# 02_memory.net
KiCad netlist of a schematic drawn in Altium Designer
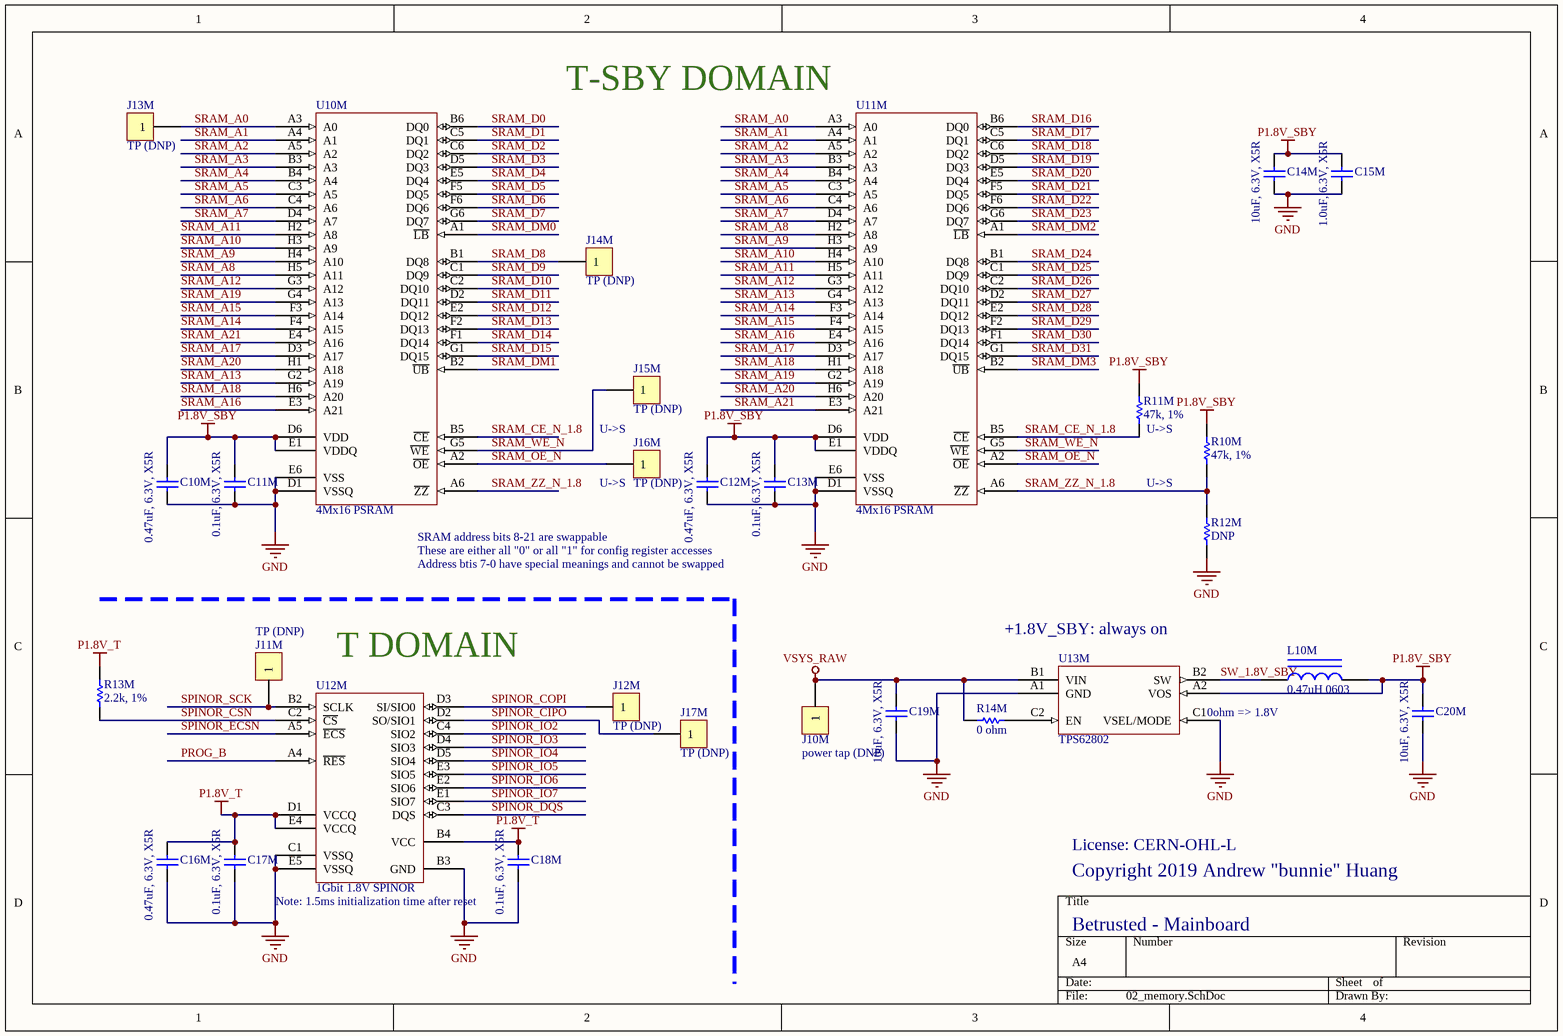
[diagram p0: 02_memory.SchDoc]

(export (version "E")
  (design (tool "Eeschema 10.0.6"))
  (components
    (comp (ref "C10M")
      (value "0.47uF, 6.3V, X5R")
      (footprint "B_CAP0201")
      (description "Capacitor (Semiconductor SIM Model)")
      (fields (field (name "MPN") "CL03A474KQ3NNNH"))
      (libsource (lib "Miscellaneous Devices") (part "Cap Semi"))
    )
    (comp (ref "C11M")
      (value "0.1uF, 6.3V, X5R")
      (footprint "B_CAP0201")
      (description "Capacitor (Semiconductor SIM Model)")
      (fields (field (name "MPN") "CL03A104KQ3NNNC"))
      (libsource (lib "Miscellaneous Devices") (part "Cap Semi"))
    )
    (comp (ref "C12M")
      (value "0.47uF, 6.3V, X5R")
      (footprint "B_CAP0201")
      (description "Capacitor (Semiconductor SIM Model)")
      (fields (field (name "MPN") "CL03A474KQ3NNNH"))
      (libsource (lib "Miscellaneous Devices") (part "Cap Semi"))
    )
    (comp (ref "C13M")
      (value "0.1uF, 6.3V, X5R")
      (footprint "B_CAP0201")
      (description "Capacitor (Semiconductor SIM Model)")
      (fields (field (name "MPN") "CL03A104KQ3NNNC"))
      (libsource (lib "Miscellaneous Devices") (part "Cap Semi"))
    )
    (comp (ref "C14M")
      (value "10uF, 6.3V, X5R")
      (footprint "B_CAP0603")
      (description "Capacitor (Semiconductor SIM Model)")
      (fields (field (name "MPN") "CL10A106MQ8NNNC"))
      (libsource (lib "Miscellaneous Devices") (part "Cap Semi"))
    )
    (comp (ref "C15M")
      (value "1.0uF, 6.3V, X5R")
      (footprint "B_CAP0201")
      (description "Capacitor (Semiconductor SIM Model)")
      (fields (field (name "MPN") "GRM033R60J105MEA2D"))
      (libsource (lib "Miscellaneous Devices") (part "Cap Semi"))
    )
    (comp (ref "C16M")
      (value "0.47uF, 6.3V, X5R")
      (footprint "B_CAP0201")
      (description "Capacitor (Semiconductor SIM Model)")
      (fields (field (name "MPN") "CL03A474KQ3NNNH"))
      (libsource (lib "Miscellaneous Devices") (part "Cap Semi"))
    )
    (comp (ref "C17M")
      (value "0.1uF, 6.3V, X5R")
      (footprint "B_CAP0201")
      (description "Capacitor (Semiconductor SIM Model)")
      (fields (field (name "MPN") "CL03A104KQ3NNNC"))
      (libsource (lib "Miscellaneous Devices") (part "Cap Semi"))
    )
    (comp (ref "C18M")
      (value "0.1uF, 6.3V, X5R")
      (footprint "B_CAP0201")
      (description "Capacitor (Semiconductor SIM Model)")
      (fields (field (name "MPN") "CL03A104KQ3NNNC"))
      (libsource (lib "Miscellaneous Devices") (part "Cap Semi"))
    )
    (comp (ref "C19M")
      (value "10uF, 6.3V, X5R")
      (footprint "B_CAP0603")
      (description "Capacitor (Semiconductor SIM Model)")
      (fields (field (name "MPN") "CL10A106MQ8NNNC"))
      (libsource (lib "Miscellaneous Devices") (part "Cap Semi"))
    )
    (comp (ref "C20M")
      (value "10uF, 6.3V, X5R")
      (footprint "B_CAP0603")
      (description "Capacitor (Semiconductor SIM Model)")
      (fields (field (name "MPN") "CL10A106MQ8NNNC"))
      (libsource (lib "Miscellaneous Devices") (part "Cap Semi"))
    )
    (comp (ref "J10M")
      (value "power tap (DNP)")
      (footprint "RESTAP-0603")
      (description "Connector")
      (fields (field (name "MPN") "DNP"))
      (libsource (lib "") (part "CON1_2"))
    )
    (comp (ref "J11M")
      (value "TP (DNP)")
      (footprint "TP_0.4x0.4_SMT")
      (description "Connector")
      (fields (field (name "MPN") "DNP"))
      (libsource (lib "") (part "CON1_1"))
    )
    (comp (ref "J12M")
      (value "TP (DNP)")
      (footprint "TP_0.4x0.4_SMT")
      (description "Connector")
      (fields (field (name "MPN") "DNP"))
      (libsource (lib "*") (part "CON1"))
    )
    (comp (ref "J13M")
      (value "TP (DNP)")
      (footprint "TP_0.4x0.4_SMT")
      (description "Connector")
      (fields (field (name "MPN") "DNP"))
      (libsource (lib "") (part "CON1_3"))
    )
    (comp (ref "J14M")
      (value "TP (DNP)")
      (footprint "TP_0.4x0.4_SMT")
      (description "Connector")
      (fields (field (name "MPN") "DNP"))
      (libsource (lib "*") (part "CON1"))
    )
    (comp (ref "J15M")
      (value "TP (DNP)")
      (footprint "TP_0.4x0.4_SMT")
      (description "Connector")
      (fields (field (name "MPN") "DNP"))
      (libsource (lib "*") (part "CON1"))
    )
    (comp (ref "J16M")
      (value "TP (DNP)")
      (footprint "TP_0.4x0.4_SMT")
      (description "Connector")
      (fields (field (name "MPN") "DNP"))
      (libsource (lib "*") (part "CON1"))
    )
    (comp (ref "J17M")
      (value "TP (DNP)")
      (footprint "TP_0.4x0.4_SMT")
      (description "Connector")
      (fields (field (name "MPN") "DNP"))
      (libsource (lib "*") (part "CON1"))
    )
    (comp (ref "L10M")
      (value "0.47uH 0603")
      (footprint "B_IND0603")
      (description "Magnetic-Core Inductor")
      (fields (field (name "MPN") "TFM160808ALC-R47MTAA"))
      (libsource (lib "Miscellaneous Devices") (part "Inductor Iron"))
    )
    (comp (ref "R10M")
      (value "47k, 1%")
      (footprint "B_RES0201")
      (description "Resistor")
      (fields (field (name "MPN") "ANY"))
      (libsource (lib "Miscellaneous Devices") (part "Res1"))
    )
    (comp (ref "R11M")
      (value "47k, 1%")
      (footprint "B_RES0201")
      (description "Resistor")
      (fields (field (name "MPN") "ANY"))
      (libsource (lib "Miscellaneous Devices") (part "Res1"))
    )
    (comp (ref "R12M")
      (value "DNP")
      (footprint "B_RES0201")
      (description "Resistor")
      (fields (field (name "MPN") "ANY"))
      (libsource (lib "Miscellaneous Devices") (part "Res1"))
    )
    (comp (ref "R13M")
      (value "2.2k, 1%")
      (footprint "B_RES0201")
      (description "Resistor")
      (fields (field (name "MPN") "ANY"))
      (libsource (lib "Miscellaneous Devices") (part "Res1"))
    )
    (comp (ref "R14M")
      (value "0 ohm")
      (footprint "B_RES0201")
      (description "Resistor")
      (fields (field (name "MPN") "ANY"))
      (libsource (lib "Miscellaneous Devices") (part "Res1"))
    )
    (comp (ref "U10M")
      (value "4Mx16 PSRAM")
      (footprint "BGA48C75P6X8_600X800X120")
      (fields (field (name "MPN") "IS66WVE4M16EALL-70BLI"))
      (libsource (lib "altium-import") (part "root_0_IS66WVE4M16_"))
    )
    (comp (ref "U11M")
      (value "4Mx16 PSRAM")
      (footprint "BGA48C75P6X8_600X800X120")
      (fields (field (name "MPN") "IS66WVE4M16EALL-70BLI"))
      (libsource (lib "altium-import") (part "root_0_IS66WVE4M16_"))
    )
    (comp (ref "U12M")
      (value "1Gbit 1.8V SPINOR")
      (footprint "BGA24C100P5X5_600X800X120")
      (description "1.8V 1Gbit x1/x8 OctaFlash SPINOR")
      (fields (field (name "MPN") "MX66UM1G45GXDI00"))
      (libsource (lib "commonsch-new") (part "MX66UM1G45G"))
    )
    (comp (ref "U13M")
      (value "TPS62802")
      (footprint "BGA6C35P2X3_70X105X40_NSMD")
      (description "Buck regulator, 4MHz, 0.6A, 1.8V-3.3V, low Iq")
      (fields (field (name "MPN") "TPS62802YKAR"))
      (libsource (lib "altium-import") (part "root_0_TPS62802_"))
    )
  )
  (nets
    (net (code "1") (name "/PROG_B") (class "Default")
      (node (ref "U12M") (pin "A4") (pinfunction "~{RES}_A4") (pintype "input"))
    )
    (net (code "2") (name "/SPINOR_CIPO") (class "Default")
      (node (ref "J17M") (pin "1") (pinfunction "1_1") (pintype "passive"))
      (node (ref "U12M") (pin "D2") (pinfunction "SO/SIO1_D2") (pintype "bidirectional"))
    )
    (net (code "3") (name "/SPINOR_COPI") (class "Default")
      (node (ref "J12M") (pin "1") (pinfunction "1_1") (pintype "passive"))
      (node (ref "U12M") (pin "D3") (pinfunction "SI/SIO0_D3") (pintype "bidirectional"))
    )
    (net (code "4") (name "/SPINOR_CSN") (class "Default")
      (node (ref "R13M") (pin "1") (pinfunction "1_1") (pintype "passive"))
      (node (ref "U12M") (pin "C2") (pinfunction "~{CS}_C2") (pintype "input"))
    )
    (net (code "5") (name "/SPINOR_DQS") (class "Default")
      (node (ref "U12M") (pin "C3") (pinfunction "DQS_C3") (pintype "bidirectional"))
    )
    (net (code "6") (name "/SPINOR_ECSN") (class "Default")
      (node (ref "U12M") (pin "A5") (pinfunction "~{ECS}_A5") (pintype "input"))
    )
    (net (code "7") (name "/SPINOR_IO2") (class "Default")
      (node (ref "U12M") (pin "C4") (pinfunction "SIO2_C4") (pintype "bidirectional"))
    )
    (net (code "8") (name "/SPINOR_IO3") (class "Default")
      (node (ref "U12M") (pin "D4") (pinfunction "SIO3_D4") (pintype "bidirectional"))
    )
    (net (code "9") (name "/SPINOR_IO4") (class "Default")
      (node (ref "U12M") (pin "D5") (pinfunction "SIO4_D5") (pintype "bidirectional"))
    )
    (net (code "10") (name "/SPINOR_IO5") (class "Default")
      (node (ref "U12M") (pin "E3") (pinfunction "SIO5_E3") (pintype "bidirectional"))
    )
    (net (code "11") (name "/SPINOR_IO6") (class "Default")
      (node (ref "U12M") (pin "E2") (pinfunction "SIO6_E2") (pintype "bidirectional"))
    )
    (net (code "12") (name "/SPINOR_IO7") (class "Default")
      (node (ref "U12M") (pin "E1") (pinfunction "SIO7_E1") (pintype "bidirectional"))
    )
    (net (code "13") (name "/SPINOR_SCK") (class "Default")
      (node (ref "J11M") (pin "1") (pinfunction "1_1") (pintype "passive"))
      (node (ref "U12M") (pin "B2") (pinfunction "SCLK_B2") (pintype "input"))
    )
    (net (code "14") (name "/SRAM_A0") (class "Default")
      (node (ref "J13M") (pin "1") (pinfunction "1_1") (pintype "passive"))
      (node (ref "U10M") (pin "A3") (pinfunction "A0_A3") (pintype "input"))
      (node (ref "U11M") (pin "A3") (pinfunction "A0_A3") (pintype "input"))
    )
    (net (code "15") (name "/SRAM_A1") (class "Default")
      (node (ref "U10M") (pin "A4") (pinfunction "A1_A4") (pintype "input"))
      (node (ref "U11M") (pin "A4") (pinfunction "A1_A4") (pintype "input"))
    )
    (net (code "16") (name "/SRAM_A2") (class "Default")
      (node (ref "U10M") (pin "A5") (pinfunction "A2_A5") (pintype "input"))
      (node (ref "U11M") (pin "A5") (pinfunction "A2_A5") (pintype "input"))
    )
    (net (code "17") (name "/SRAM_A3") (class "Default")
      (node (ref "U10M") (pin "B3") (pinfunction "A3_B3") (pintype "input"))
      (node (ref "U11M") (pin "B3") (pinfunction "A3_B3") (pintype "input"))
    )
    (net (code "18") (name "/SRAM_A4") (class "Default")
      (node (ref "U10M") (pin "B4") (pinfunction "A4_B4") (pintype "input"))
      (node (ref "U11M") (pin "B4") (pinfunction "A4_B4") (pintype "input"))
    )
    (net (code "19") (name "/SRAM_A5") (class "Default")
      (node (ref "U10M") (pin "C3") (pinfunction "A5_C3") (pintype "input"))
      (node (ref "U11M") (pin "C3") (pinfunction "A5_C3") (pintype "input"))
    )
    (net (code "20") (name "/SRAM_A6") (class "Default")
      (node (ref "U10M") (pin "C4") (pinfunction "A6_C4") (pintype "input"))
      (node (ref "U11M") (pin "C4") (pinfunction "A6_C4") (pintype "input"))
    )
    (net (code "21") (name "/SRAM_A7") (class "Default")
      (node (ref "U10M") (pin "D4") (pinfunction "A7_D4") (pintype "input"))
      (node (ref "U11M") (pin "D4") (pinfunction "A7_D4") (pintype "input"))
    )
    (net (code "22") (name "/SRAM_A8") (class "Default")
      (node (ref "U10M") (pin "H5") (pinfunction "A11_H5") (pintype "input"))
      (node (ref "U11M") (pin "H2") (pinfunction "A8_H2") (pintype "input"))
    )
    (net (code "23") (name "/SRAM_A9") (class "Default")
      (node (ref "U10M") (pin "H4") (pinfunction "A10_H4") (pintype "input"))
      (node (ref "U11M") (pin "H3") (pinfunction "A9_H3") (pintype "input"))
    )
    (net (code "24") (name "/SRAM_A10") (class "Default")
      (node (ref "U10M") (pin "H3") (pinfunction "A9_H3") (pintype "input"))
      (node (ref "U11M") (pin "H4") (pinfunction "A10_H4") (pintype "input"))
    )
    (net (code "25") (name "/SRAM_A11") (class "Default")
      (node (ref "U10M") (pin "H2") (pinfunction "A8_H2") (pintype "input"))
      (node (ref "U11M") (pin "H5") (pinfunction "A11_H5") (pintype "input"))
    )
    (net (code "26") (name "/SRAM_A12") (class "Default")
      (node (ref "U10M") (pin "G3") (pinfunction "A12_G3") (pintype "input"))
      (node (ref "U11M") (pin "G3") (pinfunction "A12_G3") (pintype "input"))
    )
    (net (code "27") (name "/SRAM_A13") (class "Default")
      (node (ref "U10M") (pin "G2") (pinfunction "A19_G2") (pintype "input"))
      (node (ref "U11M") (pin "G4") (pinfunction "A13_G4") (pintype "input"))
    )
    (net (code "28") (name "/SRAM_A14") (class "Default")
      (node (ref "U10M") (pin "F4") (pinfunction "A15_F4") (pintype "input"))
      (node (ref "U11M") (pin "F3") (pinfunction "A14_F3") (pintype "input"))
    )
    (net (code "29") (name "/SRAM_A15") (class "Default")
      (node (ref "U10M") (pin "F3") (pinfunction "A14_F3") (pintype "input"))
      (node (ref "U11M") (pin "F4") (pinfunction "A15_F4") (pintype "input"))
    )
    (net (code "30") (name "/SRAM_A16") (class "Default")
      (node (ref "U10M") (pin "E3") (pinfunction "A21_E3") (pintype "input"))
      (node (ref "U11M") (pin "E4") (pinfunction "A16_E4") (pintype "input"))
    )
    (net (code "31") (name "/SRAM_A17") (class "Default")
      (node (ref "U10M") (pin "D3") (pinfunction "A17_D3") (pintype "input"))
      (node (ref "U11M") (pin "D3") (pinfunction "A17_D3") (pintype "input"))
    )
    (net (code "32") (name "/SRAM_A18") (class "Default")
      (node (ref "U10M") (pin "H6") (pinfunction "A20_H6") (pintype "input"))
      (node (ref "U11M") (pin "H1") (pinfunction "A18_H1") (pintype "input"))
    )
    (net (code "33") (name "/SRAM_A19") (class "Default")
      (node (ref "U10M") (pin "G4") (pinfunction "A13_G4") (pintype "input"))
      (node (ref "U11M") (pin "G2") (pinfunction "A19_G2") (pintype "input"))
    )
    (net (code "34") (name "/SRAM_A20") (class "Default")
      (node (ref "U10M") (pin "H1") (pinfunction "A18_H1") (pintype "input"))
      (node (ref "U11M") (pin "H6") (pinfunction "A20_H6") (pintype "input"))
    )
    (net (code "35") (name "/SRAM_A21") (class "Default")
      (node (ref "U10M") (pin "E4") (pinfunction "A16_E4") (pintype "input"))
      (node (ref "U11M") (pin "E3") (pinfunction "A21_E3") (pintype "input"))
    )
    (net (code "36") (name "/SRAM_CE_N_1.8") (class "Default")
      (node (ref "R11M") (pin "2") (pinfunction "2_2") (pintype "passive"))
      (node (ref "U10M") (pin "B5") (pinfunction "~{CE}_B5") (pintype "input"))
      (node (ref "U11M") (pin "B5") (pinfunction "~{CE}_B5") (pintype "input"))
    )
    (net (code "37") (name "/SRAM_D0") (class "Default")
      (node (ref "U10M") (pin "B6") (pinfunction "DQ0_B6") (pintype "bidirectional"))
    )
    (net (code "38") (name "/SRAM_D1") (class "Default")
      (node (ref "U10M") (pin "C5") (pinfunction "DQ1_C5") (pintype "bidirectional"))
    )
    (net (code "39") (name "/SRAM_D2") (class "Default")
      (node (ref "U10M") (pin "C6") (pinfunction "DQ2_C6") (pintype "bidirectional"))
    )
    (net (code "40") (name "/SRAM_D3") (class "Default")
      (node (ref "U10M") (pin "D5") (pinfunction "DQ3_D5") (pintype "bidirectional"))
    )
    (net (code "41") (name "/SRAM_D4") (class "Default")
      (node (ref "U10M") (pin "E5") (pinfunction "DQ4_E5") (pintype "bidirectional"))
    )
    (net (code "42") (name "/SRAM_D5") (class "Default")
      (node (ref "U10M") (pin "F5") (pinfunction "DQ5_F5") (pintype "bidirectional"))
    )
    (net (code "43") (name "/SRAM_D6") (class "Default")
      (node (ref "U10M") (pin "F6") (pinfunction "DQ6_F6") (pintype "bidirectional"))
    )
    (net (code "44") (name "/SRAM_D7") (class "Default")
      (node (ref "U10M") (pin "G6") (pinfunction "DQ7_G6") (pintype "bidirectional"))
    )
    (net (code "45") (name "/SRAM_D8") (class "Default")
      (node (ref "J14M") (pin "1") (pinfunction "1_1") (pintype "passive"))
      (node (ref "U10M") (pin "B1") (pinfunction "DQ8_B1") (pintype "bidirectional"))
    )
    (net (code "46") (name "/SRAM_D9") (class "Default")
      (node (ref "U10M") (pin "C1") (pinfunction "DQ9_C1") (pintype "bidirectional"))
    )
    (net (code "47") (name "/SRAM_D10") (class "Default")
      (node (ref "U10M") (pin "C2") (pinfunction "DQ10_C2") (pintype "bidirectional"))
    )
    (net (code "48") (name "/SRAM_D11") (class "Default")
      (node (ref "U10M") (pin "D2") (pinfunction "DQ11_D2") (pintype "bidirectional"))
    )
    (net (code "49") (name "/SRAM_D12") (class "Default")
      (node (ref "U10M") (pin "E2") (pinfunction "DQ12_E2") (pintype "bidirectional"))
    )
    (net (code "50") (name "/SRAM_D13") (class "Default")
      (node (ref "U10M") (pin "F2") (pinfunction "DQ13_F2") (pintype "bidirectional"))
    )
    (net (code "51") (name "/SRAM_D14") (class "Default")
      (node (ref "U10M") (pin "F1") (pinfunction "DQ14_F1") (pintype "bidirectional"))
    )
    (net (code "52") (name "/SRAM_D15") (class "Default")
      (node (ref "U10M") (pin "G1") (pinfunction "DQ15_G1") (pintype "bidirectional"))
    )
    (net (code "53") (name "/SRAM_D16") (class "Default")
      (node (ref "U11M") (pin "B6") (pinfunction "DQ0_B6") (pintype "bidirectional"))
    )
    (net (code "54") (name "/SRAM_D17") (class "Default")
      (node (ref "U11M") (pin "C5") (pinfunction "DQ1_C5") (pintype "bidirectional"))
    )
    (net (code "55") (name "/SRAM_D18") (class "Default")
      (node (ref "U11M") (pin "C6") (pinfunction "DQ2_C6") (pintype "bidirectional"))
    )
    (net (code "56") (name "/SRAM_D19") (class "Default")
      (node (ref "U11M") (pin "D5") (pinfunction "DQ3_D5") (pintype "bidirectional"))
    )
    (net (code "57") (name "/SRAM_D20") (class "Default")
      (node (ref "U11M") (pin "E5") (pinfunction "DQ4_E5") (pintype "bidirectional"))
    )
    (net (code "58") (name "/SRAM_D21") (class "Default")
      (node (ref "U11M") (pin "F5") (pinfunction "DQ5_F5") (pintype "bidirectional"))
    )
    (net (code "59") (name "/SRAM_D22") (class "Default")
      (node (ref "U11M") (pin "F6") (pinfunction "DQ6_F6") (pintype "bidirectional"))
    )
    (net (code "60") (name "/SRAM_D23") (class "Default")
      (node (ref "U11M") (pin "G6") (pinfunction "DQ7_G6") (pintype "bidirectional"))
    )
    (net (code "61") (name "/SRAM_D24") (class "Default")
      (node (ref "U11M") (pin "B1") (pinfunction "DQ8_B1") (pintype "bidirectional"))
    )
    (net (code "62") (name "/SRAM_D25") (class "Default")
      (node (ref "U11M") (pin "C1") (pinfunction "DQ9_C1") (pintype "bidirectional"))
    )
    (net (code "63") (name "/SRAM_D26") (class "Default")
      (node (ref "U11M") (pin "C2") (pinfunction "DQ10_C2") (pintype "bidirectional"))
    )
    (net (code "64") (name "/SRAM_D27") (class "Default")
      (node (ref "U11M") (pin "D2") (pinfunction "DQ11_D2") (pintype "bidirectional"))
    )
    (net (code "65") (name "/SRAM_D28") (class "Default")
      (node (ref "U11M") (pin "E2") (pinfunction "DQ12_E2") (pintype "bidirectional"))
    )
    (net (code "66") (name "/SRAM_D29") (class "Default")
      (node (ref "U11M") (pin "F2") (pinfunction "DQ13_F2") (pintype "bidirectional"))
    )
    (net (code "67") (name "/SRAM_D30") (class "Default")
      (node (ref "U11M") (pin "F1") (pinfunction "DQ14_F1") (pintype "bidirectional"))
    )
    (net (code "68") (name "/SRAM_D31") (class "Default")
      (node (ref "U11M") (pin "G1") (pinfunction "DQ15_G1") (pintype "bidirectional"))
    )
    (net (code "69") (name "/SRAM_DM0") (class "Default")
      (node (ref "U10M") (pin "A1") (pinfunction "~{LB}_A1") (pintype "input"))
    )
    (net (code "70") (name "/SRAM_DM1") (class "Default")
      (node (ref "U10M") (pin "B2") (pinfunction "~{UB}_B2") (pintype "input"))
    )
    (net (code "71") (name "/SRAM_DM2") (class "Default")
      (node (ref "U11M") (pin "A1") (pinfunction "~{LB}_A1") (pintype "input"))
    )
    (net (code "72") (name "/SRAM_DM3") (class "Default")
      (node (ref "U11M") (pin "B2") (pinfunction "~{UB}_B2") (pintype "input"))
    )
    (net (code "73") (name "/SRAM_OE_N") (class "Default")
      (node (ref "J16M") (pin "1") (pinfunction "1_1") (pintype "passive"))
      (node (ref "U10M") (pin "A2") (pinfunction "~{OE}_A2") (pintype "input"))
      (node (ref "U11M") (pin "A2") (pinfunction "~{OE}_A2") (pintype "input"))
    )
    (net (code "74") (name "/SRAM_WE_N") (class "Default")
      (node (ref "J15M") (pin "1") (pinfunction "1_1") (pintype "passive"))
      (node (ref "U10M") (pin "G5") (pinfunction "~{WE}_G5") (pintype "input"))
      (node (ref "U11M") (pin "G5") (pinfunction "~{WE}_G5") (pintype "input"))
    )
    (net (code "75") (name "/SRAM_ZZ_N_1.8") (class "Default")
      (node (ref "R10M") (pin "2") (pinfunction "2_2") (pintype "passive"))
      (node (ref "R12M") (pin "1") (pinfunction "1_1") (pintype "passive"))
      (node (ref "U10M") (pin "A6") (pinfunction "~{ZZ}_A6") (pintype "input"))
      (node (ref "U11M") (pin "A6") (pinfunction "~{ZZ}_A6") (pintype "input"))
    )
    (net (code "76") (name "/SW_1.8V_SBY") (class "Default")
      (node (ref "L10M") (pin "1") (pinfunction "1_1") (pintype "passive"))
      (node (ref "U13M") (pin "B2") (pinfunction "SW_B2") (pintype "output"))
    )
    (net (code "77") (name "GND") (class "Default")
      (node (ref "C10M") (pin "2") (pinfunction "2_2") (pintype "passive"))
      (node (ref "C11M") (pin "2") (pinfunction "2_2") (pintype "passive"))
      (node (ref "C12M") (pin "2") (pinfunction "2_2") (pintype "passive"))
      (node (ref "C13M") (pin "2") (pinfunction "2_2") (pintype "passive"))
      (node (ref "C14M") (pin "2") (pinfunction "2_2") (pintype "passive"))
      (node (ref "C15M") (pin "1") (pinfunction "1_1") (pintype "passive"))
      (node (ref "C16M") (pin "2") (pinfunction "2_2") (pintype "passive"))
      (node (ref "C17M") (pin "2") (pinfunction "2_2") (pintype "passive"))
      (node (ref "C18M") (pin "2") (pinfunction "2_2") (pintype "passive"))
      (node (ref "C19M") (pin "2") (pinfunction "2_2") (pintype "passive"))
      (node (ref "C20M") (pin "2") (pinfunction "2_2") (pintype "passive"))
      (node (ref "R12M") (pin "2") (pinfunction "2_2") (pintype "passive"))
      (node (ref "U10M") (pin "D1") (pinfunction "VSSQ_D1") (pintype "power_in"))
      (node (ref "U10M") (pin "E6") (pinfunction "VSS_E6") (pintype "power_in"))
      (node (ref "U11M") (pin "D1") (pinfunction "VSSQ_D1") (pintype "power_in"))
      (node (ref "U11M") (pin "E6") (pinfunction "VSS_E6") (pintype "power_in"))
      (node (ref "U12M") (pin "B3") (pinfunction "GND_B3") (pintype "power_in"))
      (node (ref "U12M") (pin "C1") (pinfunction "VSSQ_C1") (pintype "power_in"))
      (node (ref "U12M") (pin "E5") (pinfunction "VSSQ_E5") (pintype "power_in"))
      (node (ref "U13M") (pin "A1") (pinfunction "GND_A1") (pintype "power_in"))
      (node (ref "U13M") (pin "C1") (pinfunction "VSEL/MODE_C1") (pintype "input"))
    )
    (net (code "78") (name "Net-(U13M-EN)") (class "Default")
      (node (ref "R14M") (pin "2") (pinfunction "2_2") (pintype "passive"))
      (node (ref "U13M") (pin "C2") (pinfunction "EN_C2") (pintype "input"))
    )
    (net (code "79") (name "P1.8V_SBY") (class "Default")
      (node (ref "C10M") (pin "1") (pinfunction "1_1") (pintype "passive"))
      (node (ref "C11M") (pin "1") (pinfunction "1_1") (pintype "passive"))
      (node (ref "C12M") (pin "1") (pinfunction "1_1") (pintype "passive"))
      (node (ref "C13M") (pin "1") (pinfunction "1_1") (pintype "passive"))
      (node (ref "C14M") (pin "1") (pinfunction "1_1") (pintype "passive"))
      (node (ref "C15M") (pin "2") (pinfunction "2_2") (pintype "passive"))
      (node (ref "C20M") (pin "1") (pinfunction "1_1") (pintype "passive"))
      (node (ref "L10M") (pin "2") (pinfunction "2_2") (pintype "passive"))
      (node (ref "R10M") (pin "1") (pinfunction "1_1") (pintype "passive"))
      (node (ref "R11M") (pin "1") (pinfunction "1_1") (pintype "passive"))
      (node (ref "U10M") (pin "D6") (pinfunction "VDD_D6") (pintype "power_in"))
      (node (ref "U10M") (pin "E1") (pinfunction "VDDQ_E1") (pintype "power_in"))
      (node (ref "U11M") (pin "D6") (pinfunction "VDD_D6") (pintype "power_in"))
      (node (ref "U11M") (pin "E1") (pinfunction "VDDQ_E1") (pintype "power_in"))
      (node (ref "U13M") (pin "A2") (pinfunction "VOS_A2") (pintype "input"))
    )
    (net (code "80") (name "P1.8V_T") (class "Default")
      (node (ref "C16M") (pin "1") (pinfunction "1_1") (pintype "passive"))
      (node (ref "C17M") (pin "1") (pinfunction "1_1") (pintype "passive"))
      (node (ref "C18M") (pin "1") (pinfunction "1_1") (pintype "passive"))
      (node (ref "R13M") (pin "2") (pinfunction "2_2") (pintype "passive"))
      (node (ref "U12M") (pin "B4") (pinfunction "VCC_B4") (pintype "power_in"))
      (node (ref "U12M") (pin "D1") (pinfunction "VCCQ_D1") (pintype "power_in"))
      (node (ref "U12M") (pin "E4") (pinfunction "VCCQ_E4") (pintype "power_in"))
    )
    (net (code "81") (name "VSYS_RAW") (class "Default")
      (node (ref "C19M") (pin "1") (pinfunction "1_1") (pintype "passive"))
      (node (ref "J10M") (pin "1") (pinfunction "1_1") (pintype "passive"))
      (node (ref "R14M") (pin "1") (pinfunction "1_1") (pintype "passive"))
      (node (ref "U13M") (pin "B1") (pinfunction "VIN_B1") (pintype "power_in"))
    )
  )
)
